# I2C_To_ADC_Adapter.net
KiCad netlist of a schematic drawn in EAGLE
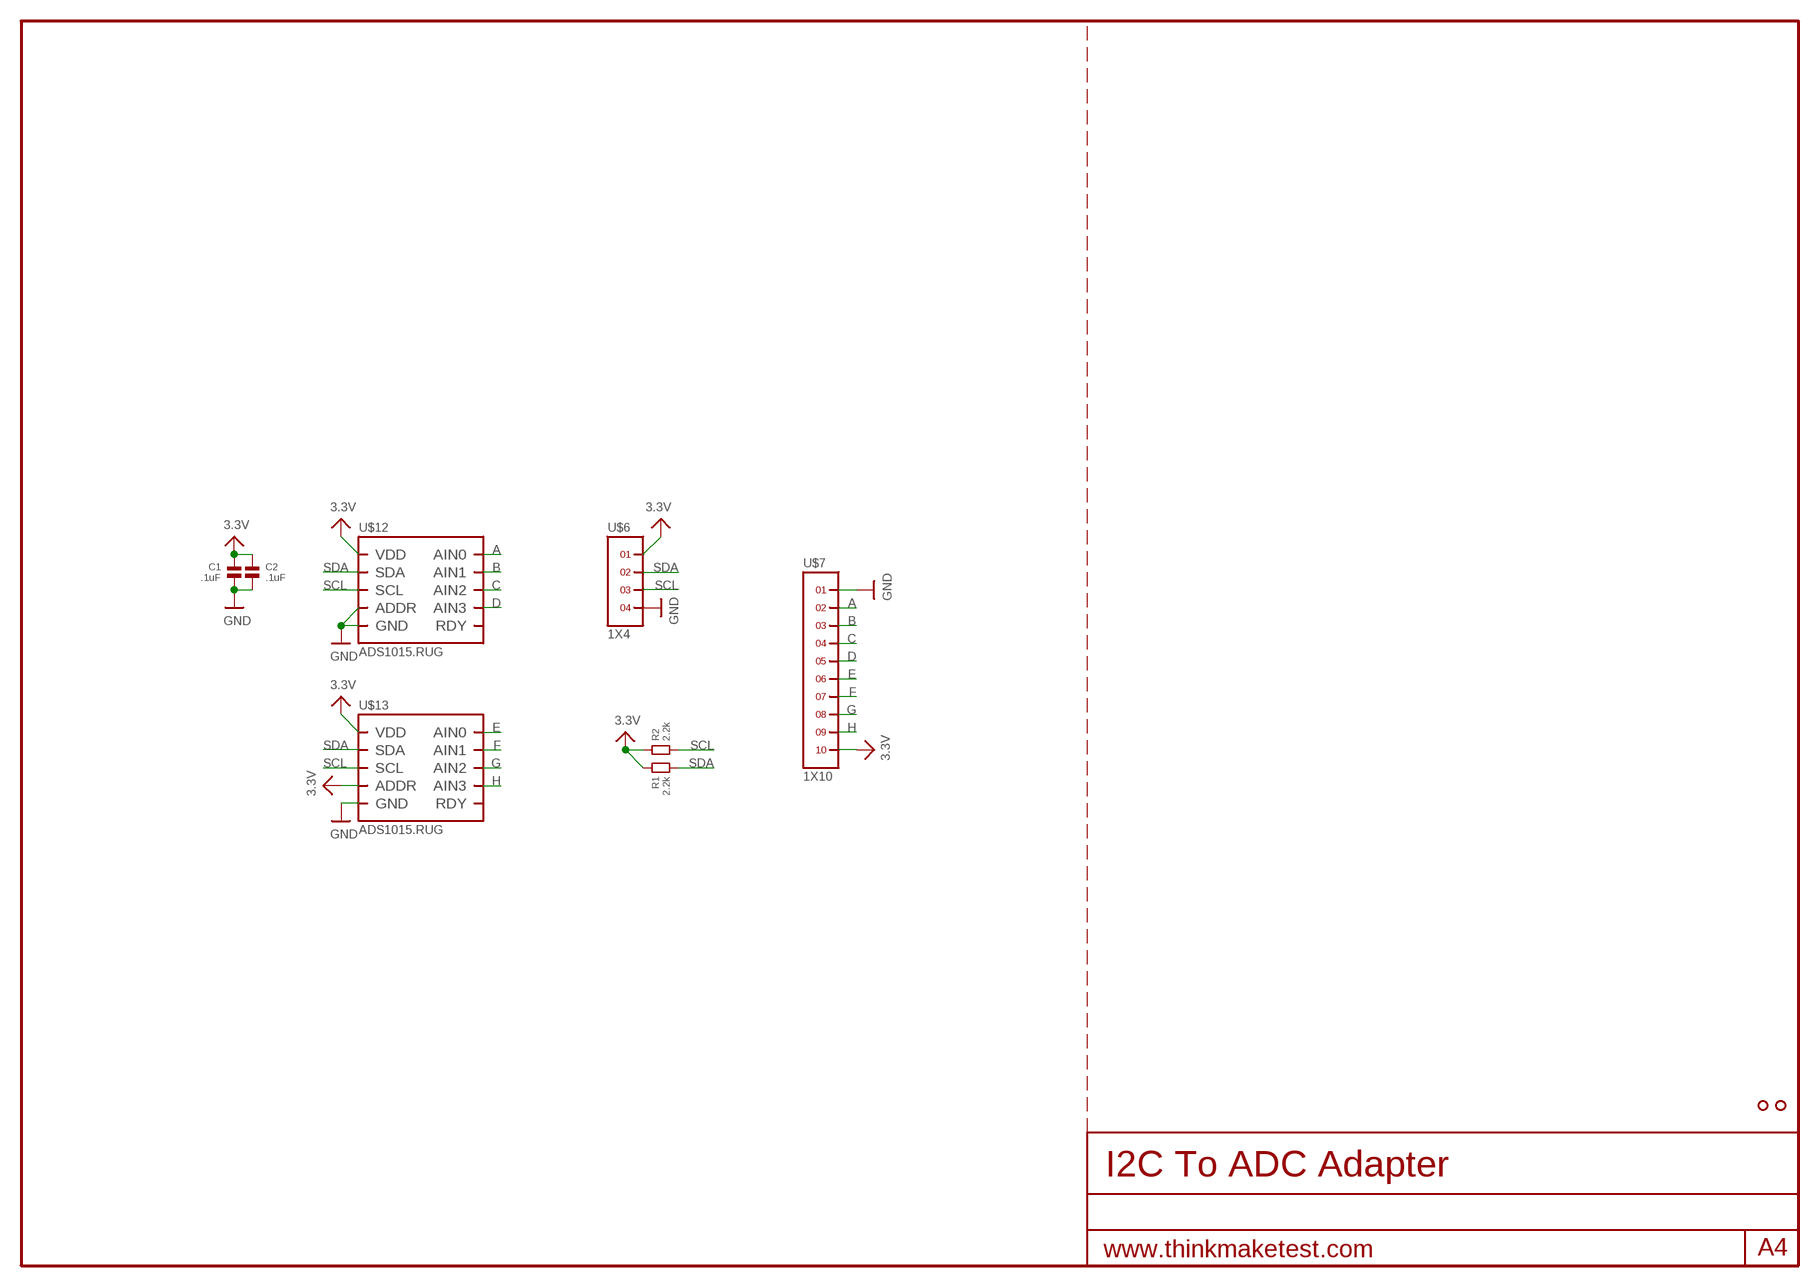
[diagram p0: schematic, sheet 1]

(export (version "E")
  (design (tool "Eeschema 10.0.6"))
  (components
    (comp (ref "C1")
      (value ".1uF")
      (footprint "eagle-import:0603")
      (libsource (lib "eagle-import") (part "CAPACITOR.0603"))
    )
    (comp (ref "C2")
      (value ".1uF")
      (footprint "eagle-import:0603")
      (libsource (lib "eagle-import") (part "CAPACITOR.0603"))
    )
    (comp (ref "R1")
      (value "2.2k")
      (footprint "eagle-import:0603")
      (libsource (lib "eagle-import") (part "RESISTOR.0603"))
    )
    (comp (ref "R2")
      (value "2.2k")
      (footprint "eagle-import:0603")
      (libsource (lib "eagle-import") (part "RESISTOR.0603"))
    )
    (comp (ref "U$3")
      (value "HOLE.4MM")
      (footprint "eagle-import:4MM")
      (libsource (lib "eagle-import") (part "HOLE.4MM"))
    )
    (comp (ref "U$6")
      (value "1X4")
      (footprint "eagle-import:1X4")
      (libsource (lib "eagle-import") (part "1X4"))
    )
    (comp (ref "U$7")
      (value "1X10")
      (footprint "eagle-import:1X10")
      (libsource (lib "eagle-import") (part "1X10"))
    )
    (comp (ref "U$12")
      (value "ADS1015.RUG")
      (footprint "eagle-import:RUG.10")
      (libsource (lib "eagle-import") (part "ADS1015.RUG"))
    )
    (comp (ref "U$13")
      (value "ADS1015.RUG")
      (footprint "eagle-import:RUG.10")
      (libsource (lib "eagle-import") (part "ADS1015.RUG"))
    )
    (comp (ref "U$18")
      (value "HOLE.4MM")
      (footprint "eagle-import:4MM")
      (libsource (lib "eagle-import") (part "HOLE.4MM"))
    )
  )
  (nets
    (net (code "1") (name "/A") (class "Default")
      (node (ref "U$12") (pin "4") (pinfunction "AIN0_4") (pintype "bidirectional"))
      (node (ref "U$7") (pin "2") (pinfunction "2_2") (pintype "bidirectional"))
    )
    (net (code "2") (name "/B") (class "Default")
      (node (ref "U$12") (pin "5") (pinfunction "AIN1_5") (pintype "bidirectional"))
      (node (ref "U$7") (pin "3") (pinfunction "3_3") (pintype "bidirectional"))
    )
    (net (code "3") (name "/C") (class "Default")
      (node (ref "U$12") (pin "6") (pinfunction "AIN2_6") (pintype "bidirectional"))
      (node (ref "U$7") (pin "4") (pinfunction "4_4") (pintype "bidirectional"))
    )
    (net (code "4") (name "/D") (class "Default")
      (node (ref "U$12") (pin "7") (pinfunction "AIN3_7") (pintype "bidirectional"))
      (node (ref "U$7") (pin "5") (pinfunction "5_5") (pintype "bidirectional"))
    )
    (net (code "5") (name "/E") (class "Default")
      (node (ref "U$13") (pin "4") (pinfunction "AIN0_4") (pintype "bidirectional"))
      (node (ref "U$7") (pin "6") (pinfunction "6_6") (pintype "bidirectional"))
    )
    (net (code "6") (name "/F") (class "Default")
      (node (ref "U$13") (pin "5") (pinfunction "AIN1_5") (pintype "bidirectional"))
      (node (ref "U$7") (pin "7") (pinfunction "7_7") (pintype "bidirectional"))
    )
    (net (code "7") (name "/G") (class "Default")
      (node (ref "U$13") (pin "6") (pinfunction "AIN2_6") (pintype "bidirectional"))
      (node (ref "U$7") (pin "8") (pinfunction "8_8") (pintype "bidirectional"))
    )
    (net (code "8") (name "/H") (class "Default")
      (node (ref "U$13") (pin "7") (pinfunction "AIN3_7") (pintype "bidirectional"))
      (node (ref "U$7") (pin "9") (pinfunction "9_9") (pintype "bidirectional"))
    )
    (net (code "9") (name "/SCL") (class "Default")
      (node (ref "R2") (pin "2") (pinfunction "2_2") (pintype "bidirectional"))
      (node (ref "U$12") (pin "10") (pinfunction "SCL_10") (pintype "bidirectional"))
      (node (ref "U$13") (pin "10") (pinfunction "SCL_10") (pintype "bidirectional"))
      (node (ref "U$6") (pin "3") (pinfunction "3_3") (pintype "bidirectional"))
    )
    (net (code "10") (name "/SDA") (class "Default")
      (node (ref "R1") (pin "2") (pinfunction "2_2") (pintype "bidirectional"))
      (node (ref "U$12") (pin "9") (pinfunction "SDA_9") (pintype "bidirectional"))
      (node (ref "U$13") (pin "9") (pinfunction "SDA_9") (pintype "bidirectional"))
      (node (ref "U$6") (pin "2") (pinfunction "2_2") (pintype "bidirectional"))
    )
    (net (code "11") (name "3.3V") (class "Default")
      (node (ref "C1") (pin "1") (pinfunction "1_1") (pintype "bidirectional"))
      (node (ref "C2") (pin "1") (pinfunction "1_1") (pintype "bidirectional"))
      (node (ref "R1") (pin "1") (pinfunction "1_1") (pintype "bidirectional"))
      (node (ref "R2") (pin "1") (pinfunction "1_1") (pintype "bidirectional"))
      (node (ref "U$12") (pin "8") (pinfunction "VDD_8") (pintype "bidirectional"))
      (node (ref "U$13") (pin "1") (pinfunction "ADDR_1") (pintype "bidirectional"))
      (node (ref "U$13") (pin "8") (pinfunction "VDD_8") (pintype "bidirectional"))
      (node (ref "U$6") (pin "1") (pinfunction "1_1") (pintype "bidirectional"))
      (node (ref "U$7") (pin "10") (pinfunction "10_10") (pintype "bidirectional"))
    )
    (net (code "12") (name "GND") (class "Default")
      (node (ref "C1") (pin "2") (pinfunction "2_2") (pintype "bidirectional"))
      (node (ref "C2") (pin "2") (pinfunction "2_2") (pintype "bidirectional"))
      (node (ref "U$12") (pin "1") (pinfunction "ADDR_1") (pintype "bidirectional"))
      (node (ref "U$12") (pin "3") (pinfunction "GND_3") (pintype "bidirectional"))
      (node (ref "U$13") (pin "3") (pinfunction "GND_3") (pintype "bidirectional"))
      (node (ref "U$6") (pin "4") (pinfunction "4_4") (pintype "bidirectional"))
      (node (ref "U$7") (pin "1") (pinfunction "1_1") (pintype "bidirectional"))
    )
    (net (code "13") (name "unconnected-(U$12-RDY-Pad2)") (class "Default")
      (node (ref "U$12") (pin "2") (pinfunction "RDY_2") (pintype "bidirectional"))
    )
    (net (code "14") (name "unconnected-(U$13-RDY-Pad2)") (class "Default")
      (node (ref "U$13") (pin "2") (pinfunction "RDY_2") (pintype "bidirectional"))
    )
  )
)
